# Port.net
KiCad netlist of a schematic drawn in Altium Designer
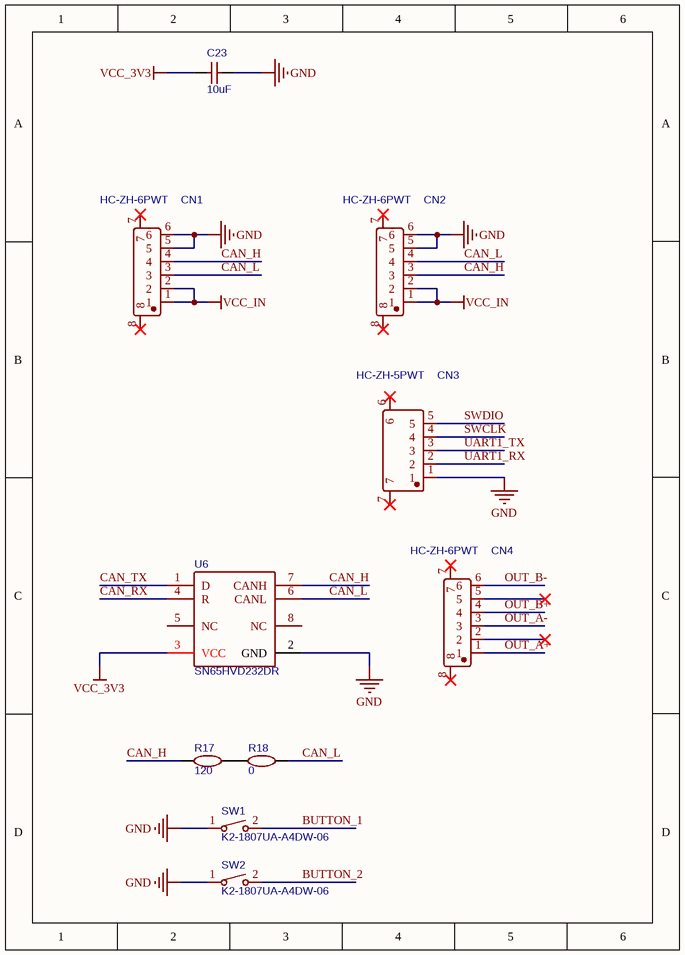
[diagram p0: Port.SchDoc]

(export (version "E")
  (design (tool "Eeschema 10.0.6"))
  (components
    (comp (ref "C23")
      (value "10uF")
      (footprint "C1206")
      (fields
        (field (name "BOM_MANUFACTURER PART") "CL31A106KBHNNNE")
        (field (name "BOM_SUPPLIER PART") "C13585")
      )
      (libsource (lib "10uF") (part "10uF"))
    )
    (comp (ref "CN1")
      (value "HC-ZH-6PWT")
      (footprint "CONN-SMD_6P-P1.50_HCTL_HC-ZH-6PWT")
      (fields (field (name "BOM_SUPPLIER PART") "C2845428") (field (name "CONTRIBUTOR") "LCSC"))
      (libsource (lib "6P 1.5mm") (part "HC-ZH-6PWT"))
    )
    (comp (ref "CN2")
      (value "HC-ZH-6PWT")
      (footprint "CONN-SMD_6P-P1.50_HCTL_HC-ZH-6PWT")
      (fields (field (name "BOM_SUPPLIER PART") "C2845428") (field (name "CONTRIBUTOR") "LCSC"))
      (libsource (lib "6P 1.5mm") (part "HC-ZH-6PWT"))
    )
    (comp (ref "CN3")
      (value "HC-ZH-5PWT")
      (footprint "CONN-SMD_5P-P1.50_HCTL_HC-ZH-5PWT")
      (fields (field (name "BOM_SUPPLIER PART") "C2845427") (field (name "CONTRIBUTOR") "LCSC"))
      (libsource (lib "5P 1.5mm") (part "HC-ZH-5PWT"))
    )
    (comp (ref "CN4")
      (value "HC-ZH-6PWT")
      (footprint "CONN-SMD_6P-P1.50_HCTL_HC-ZH-6PWT")
      (fields (field (name "BOM_SUPPLIER PART") "C2845428") (field (name "CONTRIBUTOR") "LCSC"))
      (libsource (lib "6P 1.5mm") (part "HC-ZH-6PWT"))
    )
    (comp (ref "R17")
      (value "120")
      (footprint "R0603")
      (fields
        (field (name "BOM_MANUFACTURER PART") "0603WAF1200T5E")
        (field (name "BOM_SUPPLIER PART") "C22787")
      )
      (libsource (lib "120R") (part "120"))
    )
    (comp (ref "R18")
      (value "0")
      (footprint "R0805")
      (fields
        (field (name "BOM_MANUFACTURER PART") "WR08X000PTL")
        (field (name "BOM_SUPPLIER PART") "C112378")
      )
      (libsource (lib "JUMP LINE") (part "0"))
    )
    (comp (ref "SW1")
      (value "K2-1807UA-A4DW-06")
      (footprint "KEY-SMD_L4.0-W2.9-L")
      (fields (field (name "BOM_SUPPLIER PART") "C502307") (field (name "CONTRIBUTOR") "LCSC"))
      (libsource (lib "BUTTON") (part "K2-1807UA-A4DW-06"))
    )
    (comp (ref "SW2")
      (value "K2-1807UA-A4DW-06")
      (footprint "KEY-SMD_L4.0-W2.9-L")
      (fields (field (name "BOM_SUPPLIER PART") "C502307") (field (name "CONTRIBUTOR") "LCSC"))
      (libsource (lib "BUTTON") (part "K2-1807UA-A4DW-06"))
    )
    (comp (ref "U6")
      (value "SN65HVD232DR")
      (footprint "SOIC-8_L5.0-W4.0-P1.27-LS6.0-BL")
      (fields (field (name "BOM_SUPPLIER PART") "C30530"))
      (libsource (lib "SN65HVD232DR") (part "SN65HVD232DR"))
    )
  )
  (nets
    (net (code "1") (name "/BUTTON_1") (class "Default")
      (node (ref "SW1") (pin "2") (pinfunction "2_2") (pintype "passive"))
    )
    (net (code "2") (name "/BUTTON_2") (class "Default")
      (node (ref "SW2") (pin "2") (pinfunction "2_2") (pintype "passive"))
    )
    (net (code "3") (name "/CAN_H") (class "Default")
      (node (ref "CN1") (pin "4") (pinfunction "4_4") (pintype "passive"))
      (node (ref "CN2") (pin "3") (pinfunction "3_3") (pintype "passive"))
      (node (ref "R17") (pin "1") (pinfunction "1_1") (pintype "passive"))
      (node (ref "U6") (pin "7") (pinfunction "CANH_7") (pintype "passive"))
    )
    (net (code "4") (name "/CAN_L") (class "Default")
      (node (ref "CN1") (pin "3") (pinfunction "3_3") (pintype "passive"))
      (node (ref "CN2") (pin "4") (pinfunction "4_4") (pintype "passive"))
      (node (ref "R18") (pin "2") (pinfunction "2_2") (pintype "passive"))
      (node (ref "U6") (pin "6") (pinfunction "CANL_6") (pintype "passive"))
    )
    (net (code "5") (name "/CAN_RX") (class "Default")
      (node (ref "U6") (pin "4") (pinfunction "R_4") (pintype "passive"))
    )
    (net (code "6") (name "/CAN_TX") (class "Default")
      (node (ref "U6") (pin "1") (pinfunction "D_1") (pintype "passive"))
    )
    (net (code "7") (name "/OUT_A+") (class "Default")
      (node (ref "CN4") (pin "1") (pinfunction "1_1") (pintype "passive"))
    )
    (net (code "8") (name "/OUT_A-") (class "Default")
      (node (ref "CN4") (pin "3") (pinfunction "3_3") (pintype "passive"))
    )
    (net (code "9") (name "/OUT_B+") (class "Default")
      (node (ref "CN4") (pin "4") (pinfunction "4_4") (pintype "passive"))
    )
    (net (code "10") (name "/OUT_B-") (class "Default")
      (node (ref "CN4") (pin "6") (pinfunction "6_6") (pintype "passive"))
    )
    (net (code "11") (name "/SWCLK") (class "Default")
      (node (ref "CN3") (pin "4") (pinfunction "4_4") (pintype "passive"))
    )
    (net (code "12") (name "/SWDIO") (class "Default")
      (node (ref "CN3") (pin "5") (pinfunction "5_5") (pintype "passive"))
    )
    (net (code "13") (name "/UART1_RX") (class "Default")
      (node (ref "CN3") (pin "2") (pinfunction "2_2") (pintype "passive"))
    )
    (net (code "14") (name "/UART1_TX") (class "Default")
      (node (ref "CN3") (pin "3") (pinfunction "3_3") (pintype "passive"))
    )
    (net (code "15") (name "GND") (class "Default")
      (node (ref "C23") (pin "2") (pinfunction "2_2") (pintype "passive"))
      (node (ref "CN1") (pin "5") (pinfunction "5_5") (pintype "passive"))
      (node (ref "CN1") (pin "6") (pinfunction "6_6") (pintype "passive"))
      (node (ref "CN2") (pin "5") (pinfunction "5_5") (pintype "passive"))
      (node (ref "CN2") (pin "6") (pinfunction "6_6") (pintype "passive"))
      (node (ref "CN3") (pin "1") (pinfunction "1_1") (pintype "passive"))
      (node (ref "SW1") (pin "1") (pinfunction "1_1") (pintype "passive"))
      (node (ref "SW2") (pin "1") (pinfunction "1_1") (pintype "passive"))
      (node (ref "U6") (pin "2") (pinfunction "GND_2") (pintype "passive"))
    )
    (net (code "16") (name "Net-(R17-Pad2)") (class "Default")
      (node (ref "R17") (pin "2") (pinfunction "2_2") (pintype "passive"))
      (node (ref "R18") (pin "1") (pinfunction "1_1") (pintype "passive"))
    )
    (net (code "17") (name "VCC_3V3") (class "Default")
      (node (ref "C23") (pin "1") (pinfunction "1_1") (pintype "passive"))
      (node (ref "U6") (pin "3") (pinfunction "VCC_3") (pintype "passive"))
    )
    (net (code "18") (name "VCC_IN") (class "Default")
      (node (ref "CN1") (pin "1") (pinfunction "1_1") (pintype "passive"))
      (node (ref "CN1") (pin "2") (pinfunction "2_2") (pintype "passive"))
      (node (ref "CN2") (pin "1") (pinfunction "1_1") (pintype "passive"))
      (node (ref "CN2") (pin "2") (pinfunction "2_2") (pintype "passive"))
    )
    (net (code "19") (name "unconnected-(CN1-Pad7)") (class "Default")
      (node (ref "CN1") (pin "7") (pinfunction "7_7") (pintype "passive+no_connect"))
    )
    (net (code "20") (name "unconnected-(CN1-Pad8)") (class "Default")
      (node (ref "CN1") (pin "8") (pinfunction "8_8") (pintype "passive+no_connect"))
    )
    (net (code "21") (name "unconnected-(CN2-Pad7)") (class "Default")
      (node (ref "CN2") (pin "7") (pinfunction "7_7") (pintype "passive+no_connect"))
    )
    (net (code "22") (name "unconnected-(CN2-Pad8)") (class "Default")
      (node (ref "CN2") (pin "8") (pinfunction "8_8") (pintype "passive+no_connect"))
    )
    (net (code "23") (name "unconnected-(CN3-Pad6)") (class "Default")
      (node (ref "CN3") (pin "6") (pinfunction "6_6") (pintype "passive+no_connect"))
    )
    (net (code "24") (name "unconnected-(CN3-Pad7)") (class "Default")
      (node (ref "CN3") (pin "7") (pinfunction "7_7") (pintype "passive+no_connect"))
    )
    (net (code "25") (name "unconnected-(CN4-Pad2)") (class "Default")
      (node (ref "CN4") (pin "2") (pinfunction "2_2") (pintype "passive+no_connect"))
    )
    (net (code "26") (name "unconnected-(CN4-Pad5)") (class "Default")
      (node (ref "CN4") (pin "5") (pinfunction "5_5") (pintype "passive+no_connect"))
    )
    (net (code "27") (name "unconnected-(CN4-Pad7)") (class "Default")
      (node (ref "CN4") (pin "7") (pinfunction "7_7") (pintype "passive+no_connect"))
    )
    (net (code "28") (name "unconnected-(CN4-Pad8)") (class "Default")
      (node (ref "CN4") (pin "8") (pinfunction "8_8") (pintype "passive+no_connect"))
    )
    (net (code "29") (name "unconnected-(U6-NC-Pad5)") (class "Default")
      (node (ref "U6") (pin "5") (pinfunction "NC_5") (pintype "passive"))
    )
    (net (code "30") (name "unconnected-(U6-NC-Pad8)") (class "Default")
      (node (ref "U6") (pin "8") (pinfunction "NC_8") (pintype "passive"))
    )
  )
)
